# ADC_8CH.net
KiCad netlist of a schematic drawn in Altium Designer
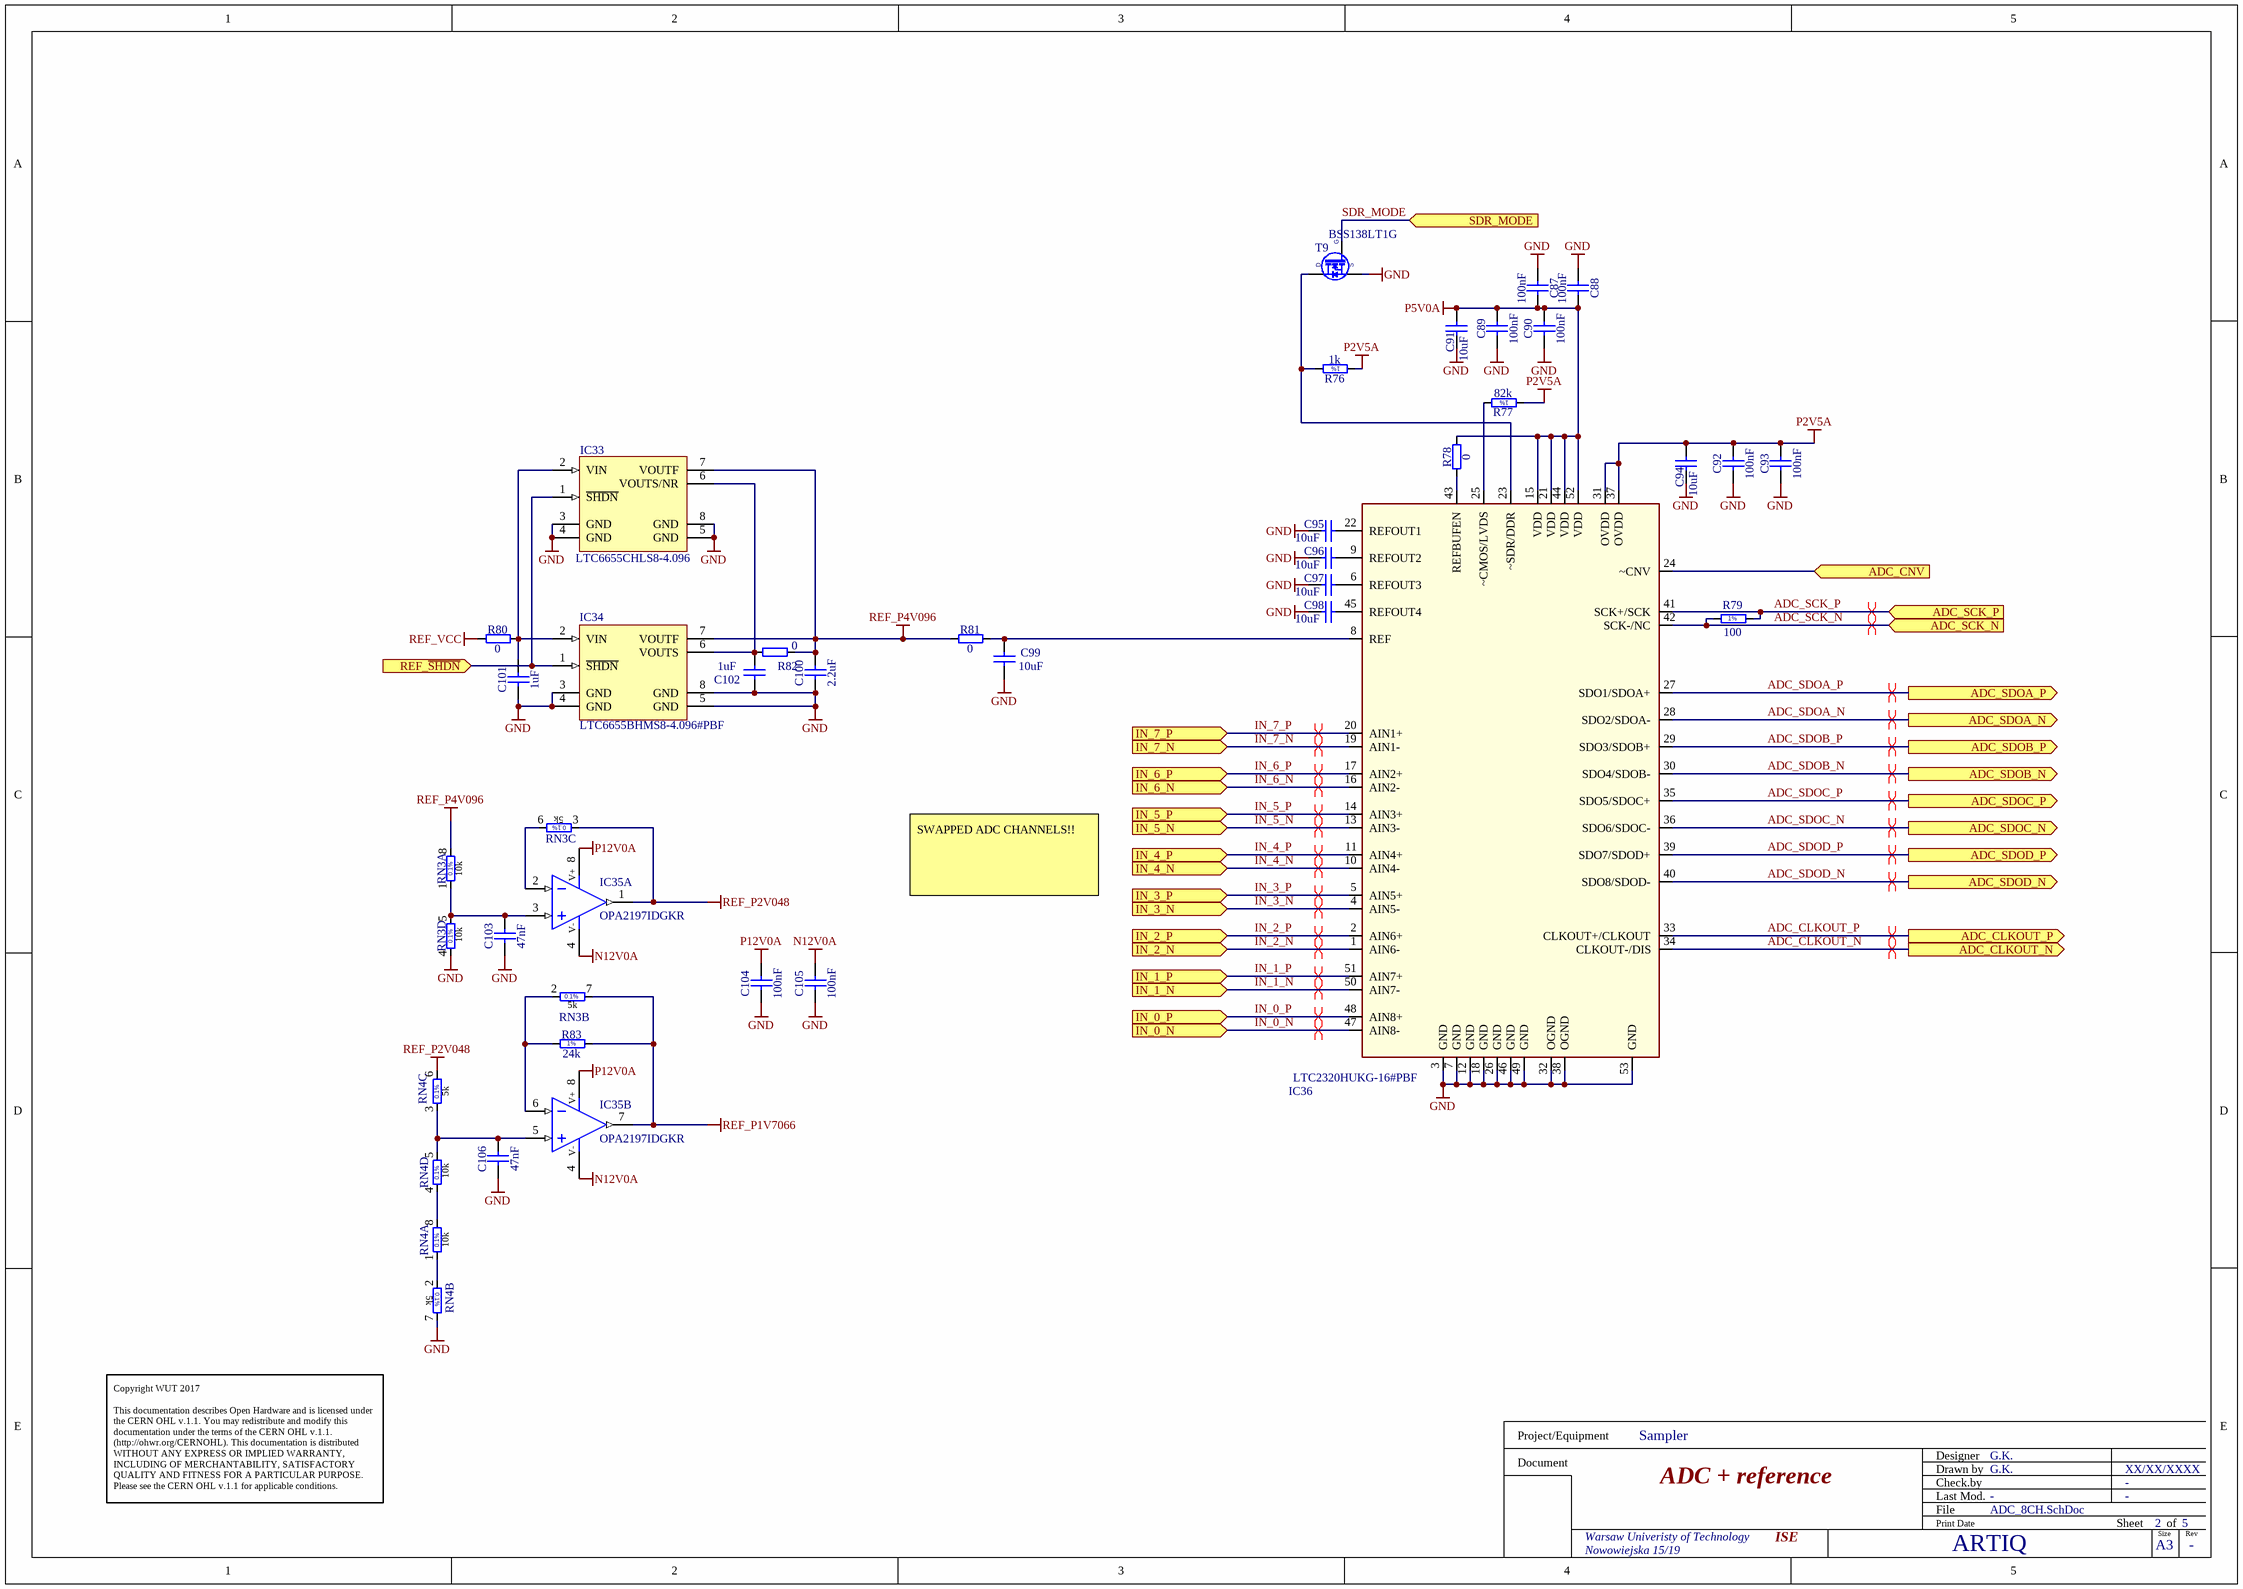
[diagram p0: ADC_8CH.SchDoc]

(export (version "E")
  (design (tool "Eeschema 10.0.6"))
  (components
    (comp (ref "C87")
      (value "100nF")
      (footprint "CAPC1608X87N")
      (description "Non-polarised capacitor")
      (fields
        (field (name "PART NUMBER") "CC0603_100NF_50V_10%_X7R")
        (field (name "VOLTAGE") "50V")
        (field (name "AUTHOR") "CERN DEM JLC")
      )
      (libsource (lib "Capacitors") (part "Capacitor - non polarized"))
    )
    (comp (ref "C88")
      (value "100nF")
      (footprint "CAPC1608X87N")
      (description "Non-polarised capacitor")
      (fields
        (field (name "PART NUMBER") "CC0603_100NF_50V_10%_X7R")
        (field (name "VOLTAGE") "50V")
        (field (name "AUTHOR") "CERN DEM JLC")
      )
      (libsource (lib "Capacitors") (part "Capacitor - non polarized"))
    )
    (comp (ref "C89")
      (value "100nF")
      (footprint "CAPC1608X87N")
      (description "Non-polarised capacitor")
      (fields
        (field (name "PART NUMBER") "CC0603_100NF_50V_10%_X7R")
        (field (name "VOLTAGE") "50V")
        (field (name "AUTHOR") "CERN DEM JLC")
      )
      (libsource (lib "Capacitors") (part "Capacitor - non polarized"))
    )
    (comp (ref "C90")
      (value "100nF")
      (footprint "CAPC1608X87N")
      (description "Non-polarised capacitor")
      (fields
        (field (name "PART NUMBER") "CC0603_100NF_50V_10%_X7R")
        (field (name "VOLTAGE") "50V")
        (field (name "AUTHOR") "CERN DEM JLC")
      )
      (libsource (lib "Capacitors") (part "Capacitor - non polarized"))
    )
    (comp (ref "C91")
      (value "10uF")
      (footprint "CAPC2012X95N")
      (description "Non-polarised capacitor")
      (fields
        (field (name "PART NUMBER") "CC0805_10UF_25V_10%_X5R")
        (field (name "VOLTAGE") "25V")
        (field (name "AUTHOR") "CERN DEM JLC")
      )
      (libsource (lib "Capacitors") (part "Capacitor - non polarized"))
    )
    (comp (ref "C92")
      (value "100nF")
      (footprint "CAPC1608X87N")
      (description "Non-polarised capacitor")
      (fields
        (field (name "PART NUMBER") "CC0603_100NF_50V_10%_X7R")
        (field (name "VOLTAGE") "50V")
        (field (name "AUTHOR") "CERN DEM JLC")
      )
      (libsource (lib "Capacitors") (part "Capacitor - non polarized"))
    )
    (comp (ref "C93")
      (value "100nF")
      (footprint "CAPC1608X87N")
      (description "Non-polarised capacitor")
      (fields
        (field (name "PART NUMBER") "CC0603_100NF_50V_10%_X7R")
        (field (name "VOLTAGE") "50V")
        (field (name "AUTHOR") "CERN DEM JLC")
      )
      (libsource (lib "Capacitors") (part "Capacitor - non polarized"))
    )
    (comp (ref "C94")
      (value "10uF")
      (footprint "CAPC2012X95N")
      (description "Non-polarised capacitor")
      (fields
        (field (name "PART NUMBER") "CC0805_10UF_25V_10%_X5R")
        (field (name "VOLTAGE") "25V")
        (field (name "AUTHOR") "CERN DEM JLC")
      )
      (libsource (lib "Capacitors") (part "Capacitor - non polarized"))
    )
    (comp (ref "C95")
      (value "10uF")
      (footprint "CAPC2012X95N")
      (description "Non-polarised capacitor")
      (fields
        (field (name "PART NUMBER") "CC0805_10UF_25V_10%_X5R")
        (field (name "VOLTAGE") "25V")
        (field (name "AUTHOR") "CERN DEM JLC")
      )
      (libsource (lib "Capacitors") (part "Capacitor - non polarized"))
    )
    (comp (ref "C96")
      (value "10uF")
      (footprint "CAPC2012X95N")
      (description "Non-polarised capacitor")
      (fields
        (field (name "PART NUMBER") "CC0805_10UF_25V_10%_X5R")
        (field (name "VOLTAGE") "25V")
        (field (name "AUTHOR") "CERN DEM JLC")
      )
      (libsource (lib "Capacitors") (part "Capacitor - non polarized"))
    )
    (comp (ref "C97")
      (value "10uF")
      (footprint "CAPC2012X95N")
      (description "Non-polarised capacitor")
      (fields
        (field (name "PART NUMBER") "CC0805_10UF_25V_10%_X5R")
        (field (name "VOLTAGE") "25V")
        (field (name "AUTHOR") "CERN DEM JLC")
      )
      (libsource (lib "Capacitors") (part "Capacitor - non polarized"))
    )
    (comp (ref "C98")
      (value "10uF")
      (footprint "CAPC2012X95N")
      (description "Non-polarised capacitor")
      (fields
        (field (name "PART NUMBER") "CC0805_10UF_25V_10%_X5R")
        (field (name "VOLTAGE") "25V")
        (field (name "AUTHOR") "CERN DEM JLC")
      )
      (libsource (lib "Capacitors") (part "Capacitor - non polarized"))
    )
    (comp (ref "C99")
      (value "10uF")
      (footprint "CAPC2012X95N")
      (description "Non-polarised capacitor")
      (fields
        (field (name "PART NUMBER") "CC0805_10UF_25V_10%_X5R")
        (field (name "VOLTAGE") "25V")
        (field (name "AUTHOR") "CERN DEM JLC")
      )
      (libsource (lib "Capacitors") (part "Capacitor - non polarized"))
    )
    (comp (ref "C100")
      (value "2.2uF")
      (footprint "CAPC1608X87N")
      (description "Non-polarised capacitor")
      (fields
        (field (name "PART NUMBER") "CC0603_2.2UF_16V_10%_X5R")
        (field (name "VOLTAGE") "16V")
        (field (name "AUTHOR") "CERN DEM JLC")
      )
      (libsource (lib "Capacitors") (part "Capacitor - non polarized"))
    )
    (comp (ref "C101")
      (value "1uF")
      (footprint "CAPC1608X87N")
      (description "Non-polarised capacitor")
      (fields
        (field (name "PART NUMBER") "CC0603_1UF_25V_10%_X7R")
        (field (name "VOLTAGE") "25V")
        (field (name "AUTHOR") "CERN DEM JLC")
      )
      (libsource (lib "Capacitors") (part "Capacitor - non polarized"))
    )
    (comp (ref "C102")
      (value "1uF")
      (footprint "CAPC1608X87N")
      (description "Non-polarised capacitor")
      (fields
        (field (name "PART NUMBER") "CC0603_1UF_25V_10%_X7R")
        (field (name "VOLTAGE") "25V")
        (field (name "AUTHOR") "CERN DEM JLC")
      )
      (libsource (lib "Capacitors") (part "Capacitor - non polarized"))
    )
    (comp (ref "C103")
      (value "47nF")
      (footprint "CAPC2012X135N")
      (description "Non-polarised capacitor")
      (fields
        (field (name "PART NUMBER") "CC0805_47NF_25V_5%_C0G")
        (field (name "VOLTAGE") "25V")
        (field (name "AUTHOR") "CERN DEM JLC")
      )
      (libsource (lib "Capacitors") (part "Capacitor - non polarized"))
    )
    (comp (ref "C104")
      (value "100nF")
      (footprint "CAPC1005X55N")
      (description "Non-polarised capacitor")
      (fields
        (field (name "PART NUMBER") "CC0402_100NF_16V_10%_X5R")
        (field (name "VOLTAGE") "16V")
        (field (name "AUTHOR") "CERN DEM JLC")
      )
      (libsource (lib "Capacitors") (part "Capacitor - non polarized"))
    )
    (comp (ref "C105")
      (value "100nF")
      (footprint "CAPC1005X55N")
      (description "Non-polarised capacitor")
      (fields
        (field (name "PART NUMBER") "CC0402_100NF_16V_10%_X5R")
        (field (name "VOLTAGE") "16V")
        (field (name "AUTHOR") "CERN DEM JLC")
      )
      (libsource (lib "Capacitors") (part "Capacitor - non polarized"))
    )
    (comp (ref "C106")
      (value "47nF")
      (footprint "CAPC2012X135N")
      (description "Non-polarised capacitor")
      (fields
        (field (name "PART NUMBER") "CC0805_47NF_25V_5%_C0G")
        (field (name "VOLTAGE") "25V")
        (field (name "AUTHOR") "CERN DEM JLC")
      )
      (libsource (lib "Capacitors") (part "Capacitor - non polarized"))
    )
    (comp (ref "IC33")
      (value "LTC6655CHLS8-4.096")
      (footprint "LCCS127P500X500X145-8N")
      (description "4.096, 1uA Precision Voltage Reference")
      (fields
        (field (name "PART NUMBER") "LTC6655CHLS8-4.096#PBF")
        (field (name "MANUFACTURER") "LINEAR TECHNOLOGY")
        (field (name "AUTHOR") "GK")
      )
      (libsource (lib "ICs_Analog_Interfaces") (part "REF_LTC6655CHLS8-4.096"))
    )
    (comp (ref "IC34")
      (value "LTC6655BHMS8-4.096#PBF")
      (footprint "SOP65P490X110-8N")
      (description "0.25ppm Noise, Low Drift Precision Buffered Voltage Reference")
      (fields (field (name "MANUFACTURER") "LINEAR TECHNOLOGY") (field (name "AUTHOR") "GK"))
      (libsource (lib "LIBRARY_SCH") (part "REF_LTC6655"))
    )
    (comp (ref "IC35")
      (value "OPA2197IDGKR")
      (footprint "SOP65P490X110-8N")
      (description "36-V, Precision, Rail-to-Rail Input Output, Low Offset Voltage Op Amp 8-VSSOP")
      (fields (field (name "MANUFACTURER") "TEXAS INSTRUMENTS") (field (name "AUTHOR") "GK"))
      (libsource (lib "LIBRARY_SCH") (part "OA_OPA2197IDGKR"))
    )
    (comp (ref "IC36")
      (value "LTC2320HUKG-16#PBF")
      (footprint "QFN50P700X800X80_HS-53M")
      (description "Octal, 16-Bit, 1.5Msps/Ch  Simultaneous Sampling ADC")
      (fields (field (name "MANUFACTURER") "LINEAR TECHNOLOGY") (field (name "AUTHOR") "GK"))
      (libsource (lib "LIBRARY_SCH") (part "ADC_LTC2320HUKG-16"))
    )
    (comp (ref "R76")
      (value "1k")
      (footprint "RESC1608X55N")
      (description "Resistor - 1%")
      (fields
        (field (name "PART NUMBER") "R0603_1K_1%_0.1W_100PPM")
        (field (name "POWER") "0.1W")
        (field (name "AUTHOR") "CERN DEM JLC")
      )
      (libsource (lib "Resistors") (part "Resistor - 1%"))
    )
    (comp (ref "R77")
      (value "82k")
      (footprint "RESC1608X55N")
      (description "Resistor - 1%")
      (fields
        (field (name "PART NUMBER") "R0603_82K_1%_0.1W_100PPM")
        (field (name "POWER") "0.1W")
        (field (name "AUTHOR") "CERN DEM JLC")
      )
      (libsource (lib "Resistors") (part "Resistor - 1%"))
    )
    (comp (ref "R78")
      (value "0")
      (footprint "RESC1005X40N")
      (description "Resistor")
      (fields
        (field (name "PART NUMBER") "R0402_0R_JUMPER")
        (field (name "MANUFACTURER") "GENERIC")
        (field (name "AUTHOR") "CERN DEM JLC")
      )
      (libsource (lib "Resistors") (part "Resistor"))
    )
    (comp (ref "R79")
      (value "100")
      (footprint "RESC1005X40N")
      (description "Resistor - 1%")
      (fields
        (field (name "PART NUMBER") "R0402_100R_1%_0.1W_100PPM")
        (field (name "POWER") "0.1W")
        (field (name "AUTHOR") "CERN DEM JLC")
      )
      (libsource (lib "Resistors") (part "Resistor - 1%"))
    )
    (comp (ref "R80")
      (value "0")
      (footprint "RESC1005X40N")
      (description "Resistor")
      (fields
        (field (name "PART NUMBER") "R0402_0R_JUMPER")
        (field (name "MANUFACTURER") "GENERIC")
        (field (name "AUTHOR") "CERN DEM JLC")
      )
      (libsource (lib "Resistors") (part "Resistor"))
    )
    (comp (ref "R81")
      (value "0")
      (footprint "RESC1005X40N")
      (description "Resistor")
      (fields
        (field (name "PART NUMBER") "R0402_0R_JUMPER")
        (field (name "MANUFACTURER") "GENERIC")
        (field (name "AUTHOR") "CERN DEM JLC")
      )
      (libsource (lib "Resistors") (part "Resistor"))
    )
    (comp (ref "R82")
      (value "0")
      (footprint "RESC1005X40N")
      (description "Resistor")
      (fields
        (field (name "PART NUMBER") "R0402_0R_JUMPER")
        (field (name "MANUFACTURER") "GENERIC")
        (field (name "AUTHOR") "CERN DEM JLC")
      )
      (libsource (lib "Resistors") (part "Resistor"))
    )
    (comp (ref "R83")
      (value "24k")
      (footprint "RESC1608X55N")
      (description "Resistor - 1%")
      (fields
        (field (name "PART NUMBER") "R0603_24K_1%_0.1W_100PPM")
        (field (name "POWER") "0.1W")
        (field (name "AUTHOR") "CERN DEM JLC")
      )
      (libsource (lib "Resistors") (part "Resistor - 1%"))
    )
    (comp (ref "RN3")
      (value "10k 5K 5K 10K")
      (footprint "SOIC127P600X175-8N")
      (description "DIL8 Resistor Network 4 Resistors 10k-5k-5k-10k 0.1%")
      (fields
        (field (name "PART NUMBER") "RN_10K_5K_VISHAY_AORN2-1AT3")
        (field (name "POWER") "4x0.1W")
        (field (name "AUTHOR") "CERN DEM JLC")
      )
      (libsource (lib "Resistors") (part "RN DIL8_4xR_10k-5k-5k-10k_0.1%"))
    )
    (comp (ref "RN4")
      (value "10k 5K 5K 10K")
      (footprint "SOIC127P600X175-8N")
      (description "DIL8 Resistor Network 4 Resistors 10k-5k-5k-10k 0.1%")
      (fields
        (field (name "PART NUMBER") "RN_10K_5K_VISHAY_AORN2-1AT3")
        (field (name "POWER") "4x0.1W")
        (field (name "AUTHOR") "CERN DEM JLC")
      )
      (libsource (lib "Resistors") (part "RN DIL8_4xR_10k-5k-5k-10k_0.1%"))
    )
    (comp (ref "T9")
      (value "BSS138LT1G")
      (footprint "SOT95P240X110-3N")
      (description "N-CHANNEL MOSFET WITH DIODE")
      (fields (field (name "MANUFACTURER") "ON SEMICONDUCTOR") (field (name "AUTHOR") "CERN DEM JLC"))
      (libsource (lib "ICs And Semiconductors") (part "N-MOSFET-D 1G 2S 3D"))
    )
  )
  (nets
    (net (code "1") (name "/ADC_CLKOUT_N") (class "Default")
      (node (ref "IC36") (pin "34") (pinfunction "CLKOUT-/DIS_34") (pintype "passive"))
    )
    (net (code "2") (name "/ADC_CLKOUT_P") (class "Default")
      (node (ref "IC36") (pin "33") (pinfunction "CLKOUT+/CLKOUT_33") (pintype "passive"))
    )
    (net (code "3") (name "/ADC_CNV") (class "Default")
      (node (ref "IC36") (pin "24") (pinfunction "~CNV_24") (pintype "passive"))
    )
    (net (code "4") (name "/ADC_SCK_N") (class "Default")
      (node (ref "IC36") (pin "42") (pinfunction "SCK-/NC_42") (pintype "passive"))
      (node (ref "R79") (pin "1") (pinfunction "1_1") (pintype "passive"))
    )
    (net (code "5") (name "/ADC_SCK_P") (class "Default")
      (node (ref "IC36") (pin "41") (pinfunction "SCK+/SCK_41") (pintype "passive"))
      (node (ref "R79") (pin "2") (pinfunction "2_2") (pintype "passive"))
    )
    (net (code "6") (name "/ADC_SDOA_N") (class "Default")
      (node (ref "IC36") (pin "28") (pinfunction "SDO2/SDOA-_28") (pintype "passive"))
    )
    (net (code "7") (name "/ADC_SDOA_P") (class "Default")
      (node (ref "IC36") (pin "27") (pinfunction "SDO1/SDOA+_27") (pintype "passive"))
    )
    (net (code "8") (name "/ADC_SDOB_N") (class "Default")
      (node (ref "IC36") (pin "30") (pinfunction "SDO4/SDOB-_30") (pintype "passive"))
    )
    (net (code "9") (name "/ADC_SDOB_P") (class "Default")
      (node (ref "IC36") (pin "29") (pinfunction "SDO3/SDOB+_29") (pintype "passive"))
    )
    (net (code "10") (name "/ADC_SDOC_N") (class "Default")
      (node (ref "IC36") (pin "36") (pinfunction "SDO6/SDOC-_36") (pintype "passive"))
    )
    (net (code "11") (name "/ADC_SDOC_P") (class "Default")
      (node (ref "IC36") (pin "35") (pinfunction "SDO5/SDOC+_35") (pintype "passive"))
    )
    (net (code "12") (name "/ADC_SDOD_N") (class "Default")
      (node (ref "IC36") (pin "40") (pinfunction "SDO8/SDOD-_40") (pintype "passive"))
    )
    (net (code "13") (name "/ADC_SDOD_P") (class "Default")
      (node (ref "IC36") (pin "39") (pinfunction "SDO7/SDOD+_39") (pintype "passive"))
    )
    (net (code "14") (name "/IN_0_N") (class "Default")
      (node (ref "IC36") (pin "47") (pinfunction "AIN8-_47") (pintype "passive"))
    )
    (net (code "15") (name "/IN_0_P") (class "Default")
      (node (ref "IC36") (pin "48") (pinfunction "AIN8+_48") (pintype "passive"))
    )
    (net (code "16") (name "/IN_1_N") (class "Default")
      (node (ref "IC36") (pin "50") (pinfunction "AIN7-_50") (pintype "passive"))
    )
    (net (code "17") (name "/IN_1_P") (class "Default")
      (node (ref "IC36") (pin "51") (pinfunction "AIN7+_51") (pintype "passive"))
    )
    (net (code "18") (name "/IN_2_N") (class "Default")
      (node (ref "IC36") (pin "1") (pinfunction "AIN6-_1") (pintype "passive"))
    )
    (net (code "19") (name "/IN_2_P") (class "Default")
      (node (ref "IC36") (pin "2") (pinfunction "AIN6+_2") (pintype "passive"))
    )
    (net (code "20") (name "/IN_3_N") (class "Default")
      (node (ref "IC36") (pin "4") (pinfunction "AIN5-_4") (pintype "passive"))
    )
    (net (code "21") (name "/IN_3_P") (class "Default")
      (node (ref "IC36") (pin "5") (pinfunction "AIN5+_5") (pintype "passive"))
    )
    (net (code "22") (name "/IN_4_N") (class "Default")
      (node (ref "IC36") (pin "10") (pinfunction "AIN4-_10") (pintype "passive"))
    )
    (net (code "23") (name "/IN_4_P") (class "Default")
      (node (ref "IC36") (pin "11") (pinfunction "AIN4+_11") (pintype "passive"))
    )
    (net (code "24") (name "/IN_5_N") (class "Default")
      (node (ref "IC36") (pin "13") (pinfunction "AIN3-_13") (pintype "passive"))
    )
    (net (code "25") (name "/IN_5_P") (class "Default")
      (node (ref "IC36") (pin "14") (pinfunction "AIN3+_14") (pintype "passive"))
    )
    (net (code "26") (name "/IN_6_N") (class "Default")
      (node (ref "IC36") (pin "16") (pinfunction "AIN2-_16") (pintype "passive"))
    )
    (net (code "27") (name "/IN_6_P") (class "Default")
      (node (ref "IC36") (pin "17") (pinfunction "AIN2+_17") (pintype "passive"))
    )
    (net (code "28") (name "/IN_7_N") (class "Default")
      (node (ref "IC36") (pin "19") (pinfunction "AIN1-_19") (pintype "passive"))
    )
    (net (code "29") (name "/IN_7_P") (class "Default")
      (node (ref "IC36") (pin "20") (pinfunction "AIN1+_20") (pintype "passive"))
    )
    (net (code "30") (name "/REF_~{SHDN}") (class "Default")
      (node (ref "IC33") (pin "1") (pinfunction "~{SHDN}_1") (pintype "input"))
      (node (ref "IC34") (pin "1") (pinfunction "~{SHDN}_1") (pintype "input"))
    )
    (net (code "31") (name "/SDR_MODE") (class "Default")
      (node (ref "T9") (pin "1") (pinfunction "G_1") (pintype "passive"))
    )
    (net (code "32") (name "GND") (class "Default")
      (node (ref "C100") (pin "1") (pinfunction "1_1") (pintype "passive"))
      (node (ref "C101") (pin "1") (pinfunction "1_1") (pintype "passive"))
      (node (ref "C102") (pin "1") (pinfunction "1_1") (pintype "passive"))
      (node (ref "C103") (pin "1") (pinfunction "1_1") (pintype "passive"))
      (node (ref "C104") (pin "1") (pinfunction "1_1") (pintype "passive"))
      (node (ref "C105") (pin "1") (pinfunction "1_1") (pintype "passive"))
      (node (ref "C106") (pin "1") (pinfunction "1_1") (pintype "passive"))
      (node (ref "C87") (pin "1") (pinfunction "1_1") (pintype "passive"))
      (node (ref "C88") (pin "1") (pinfunction "1_1") (pintype "passive"))
      (node (ref "C89") (pin "1") (pinfunction "1_1") (pintype "passive"))
      (node (ref "C90") (pin "1") (pinfunction "1_1") (pintype "passive"))
      (node (ref "C91") (pin "1") (pinfunction "1_1") (pintype "passive"))
      (node (ref "C92") (pin "1") (pinfunction "1_1") (pintype "passive"))
      (node (ref "C93") (pin "1") (pinfunction "1_1") (pintype "passive"))
      (node (ref "C94") (pin "1") (pinfunction "1_1") (pintype "passive"))
      (node (ref "C95") (pin "1") (pinfunction "1_1") (pintype "passive"))
      (node (ref "C96") (pin "1") (pinfunction "1_1") (pintype "passive"))
      (node (ref "C97") (pin "1") (pinfunction "1_1") (pintype "passive"))
      (node (ref "C98") (pin "1") (pinfunction "1_1") (pintype "passive"))
      (node (ref "C99") (pin "1") (pinfunction "1_1") (pintype "passive"))
      (node (ref "IC33") (pin "3") (pinfunction "GND_3") (pintype "power_in"))
      (node (ref "IC33") (pin "4") (pinfunction "GND_4") (pintype "power_in"))
      (node (ref "IC33") (pin "5") (pinfunction "GND_5") (pintype "power_in"))
      (node (ref "IC33") (pin "8") (pinfunction "GND_8") (pintype "power_in"))
      (node (ref "IC34") (pin "3") (pinfunction "GND_3") (pintype "power_in"))
      (node (ref "IC34") (pin "4") (pinfunction "GND_4") (pintype "power_in"))
      (node (ref "IC34") (pin "5") (pinfunction "GND_5") (pintype "power_in"))
      (node (ref "IC34") (pin "8") (pinfunction "GND_8") (pintype "power_in"))
      (node (ref "IC36") (pin "12") (pinfunction "GND_12") (pintype "passive"))
      (node (ref "IC36") (pin "18") (pinfunction "GND_18") (pintype "passive"))
      (node (ref "IC36") (pin "26") (pinfunction "GND_26") (pintype "passive"))
      (node (ref "IC36") (pin "3") (pinfunction "GND_3") (pintype "passive"))
      (node (ref "IC36") (pin "32") (pinfunction "OGND_32") (pintype "passive"))
      (node (ref "IC36") (pin "38") (pinfunction "OGND_38") (pintype "passive"))
      (node (ref "IC36") (pin "46") (pinfunction "GND_46") (pintype "passive"))
      (node (ref "IC36") (pin "49") (pinfunction "GND_49") (pintype "passive"))
      (node (ref "IC36") (pin "53") (pinfunction "GND_53") (pintype "passive"))
      (node (ref "IC36") (pin "7") (pinfunction "GND_7") (pintype "passive"))
      (node (ref "RN3") (pin "4") (pinfunction "4_4") (pintype "passive"))
      (node (ref "RN4") (pin "7") (pinfunction "7_7") (pintype "passive"))
      (node (ref "T9") (pin "2") (pinfunction "S_2") (pintype "passive"))
    )
    (net (code "33") (name "N12V0A") (class "Default")
      (node (ref "C105") (pin "2") (pinfunction "2_2") (pintype "passive"))
      (node (ref "IC35") (pin "4") (pinfunction "V-_4") (pintype "power_in"))
    )
    (net (code "34") (name "Net-(IC33-VIN)") (class "Default")
      (node (ref "C101") (pin "2") (pinfunction "2_2") (pintype "passive"))
      (node (ref "IC33") (pin "2") (pinfunction "VIN_2") (pintype "input"))
      (node (ref "IC34") (pin "2") (pinfunction "VIN_2") (pintype "input"))
      (node (ref "R80") (pin "2") (pinfunction "2_2") (pintype "passive"))
    )
    (net (code "35") (name "Net-(IC33-VOUTS{slash}NR)") (class "Default")
      (node (ref "C102") (pin "2") (pinfunction "2_2") (pintype "passive"))
      (node (ref "IC33") (pin "6") (pinfunction "VOUTS/NR_6") (pintype "power_in"))
      (node (ref "IC34") (pin "6") (pinfunction "VOUTS_6") (pintype "power_in"))
      (node (ref "R82") (pin "1") (pinfunction "1_1") (pintype "passive"))
    )
    (net (code "36") (name "Net-(IC35A-IN+)") (class "Default")
      (node (ref "C103") (pin "2") (pinfunction "2_2") (pintype "passive"))
      (node (ref "IC35") (pin "3") (pinfunction "IN+_3") (pintype "input"))
      (node (ref "RN3") (pin "1") (pinfunction "1_1") (pintype "passive"))
      (node (ref "RN3") (pin "5") (pinfunction "5_5") (pintype "passive"))
    )
    (net (code "37") (name "Net-(IC35A-IN-)") (class "Default")
      (node (ref "IC35") (pin "2") (pinfunction "IN-_2") (pintype "input"))
      (node (ref "RN3") (pin "6") (pinfunction "6_6") (pintype "passive"))
    )
    (net (code "38") (name "Net-(IC35B-IN+)") (class "Default")
      (node (ref "C106") (pin "2") (pinfunction "2_2") (pintype "passive"))
      (node (ref "IC35") (pin "5") (pinfunction "IN+_5") (pintype "input"))
      (node (ref "RN4") (pin "3") (pinfunction "3_3") (pintype "passive"))
      (node (ref "RN4") (pin "5") (pinfunction "5_5") (pintype "passive"))
    )
    (net (code "39") (name "Net-(IC35B-IN-)") (class "Default")
      (node (ref "IC35") (pin "6") (pinfunction "IN-_6") (pintype "input"))
      (node (ref "R83") (pin "1") (pinfunction "1_1") (pintype "passive"))
      (node (ref "RN3") (pin "2") (pinfunction "2_2") (pintype "passive"))
    )
    (net (code "40") (name "Net-(IC36-REF)") (class "Default")
      (node (ref "C99") (pin "2") (pinfunction "2_2") (pintype "passive"))
      (node (ref "IC36") (pin "8") (pinfunction "REF_8") (pintype "passive"))
      (node (ref "R81") (pin "2") (pinfunction "2_2") (pintype "passive"))
    )
    (net (code "41") (name "Net-(IC36-REFBUFEN)") (class "Default")
      (node (ref "IC36") (pin "43") (pinfunction "REFBUFEN_43") (pintype "passive"))
      (node (ref "R78") (pin "1") (pinfunction "1_1") (pintype "passive"))
    )
    (net (code "42") (name "Net-(IC36-REFOUT1)") (class "Default")
      (node (ref "C95") (pin "2") (pinfunction "2_2") (pintype "passive"))
      (node (ref "IC36") (pin "22") (pinfunction "REFOUT1_22") (pintype "passive"))
    )
    (net (code "43") (name "Net-(IC36-REFOUT2)") (class "Default")
      (node (ref "C96") (pin "2") (pinfunction "2_2") (pintype "passive"))
      (node (ref "IC36") (pin "9") (pinfunction "REFOUT2_9") (pintype "passive"))
    )
    (net (code "44") (name "Net-(IC36-REFOUT3)") (class "Default")
      (node (ref "C97") (pin "2") (pinfunction "2_2") (pintype "passive"))
      (node (ref "IC36") (pin "6") (pinfunction "REFOUT3_6") (pintype "passive"))
    )
    (net (code "45") (name "Net-(IC36-REFOUT4)") (class "Default")
      (node (ref "C98") (pin "2") (pinfunction "2_2") (pintype "passive"))
      (node (ref "IC36") (pin "45") (pinfunction "REFOUT4_45") (pintype "passive"))
    )
    (net (code "46") (name "Net-(IC36-~CMOS{slash}LVDS)") (class "Default")
      (node (ref "IC36") (pin "25") (pinfunction "~CMOS/LVDS_25") (pintype "passive"))
      (node (ref "R77") (pin "2") (pinfunction "2_2") (pintype "passive"))
    )
    (net (code "47") (name "Net-(IC36-~SDR{slash}DDR)") (class "Default")
      (node (ref "IC36") (pin "23") (pinfunction "~SDR/DDR_23") (pintype "passive"))
      (node (ref "R76") (pin "2") (pinfunction "2_2") (pintype "passive"))
      (node (ref "T9") (pin "3") (pinfunction "D_3") (pintype "passive"))
    )
    (net (code "48") (name "Net-(RN4-Pad1)") (class "Default")
      (node (ref "RN4") (pin "1") (pinfunction "1_1") (pintype "passive"))
      (node (ref "RN4") (pin "2") (pinfunction "2_2") (pintype "passive"))
    )
    (net (code "49") (name "Net-(RN4-Pad4)") (class "Default")
      (node (ref "RN4") (pin "4") (pinfunction "4_4") (pintype "passive"))
      (node (ref "RN4") (pin "8") (pinfunction "8_8") (pintype "passive"))
    )
    (net (code "50") (name "P2V5A") (class "Default")
      (node (ref "C92") (pin "2") (pinfunction "2_2") (pintype "passive"))
      (node (ref "C93") (pin "2") (pinfunction "2_2") (pintype "passive"))
      (node (ref "C94") (pin "2") (pinfunction "2_2") (pintype "passive"))
      (node (ref "IC36") (pin "31") (pinfunction "OVDD_31") (pintype "passive"))
      (node (ref "IC36") (pin "37") (pinfunction "OVDD_37") (pintype "passive"))
      (node (ref "R76") (pin "1") (pinfunction "1_1") (pintype "passive"))
      (node (ref "R77") (pin "1") (pinfunction "1_1") (pintype "passive"))
    )
    (net (code "51") (name "P5V0A") (class "Default")
      (node (ref "C87") (pin "2") (pinfunction "2_2") (pintype "passive"))
      (node (ref "C88") (pin "2") (pinfunction "2_2") (pintype "passive"))
      (node (ref "C89") (pin "2") (pinfunction "2_2") (pintype "passive"))
      (node (ref "C90") (pin "2") (pinfunction "2_2") (pintype "passive"))
      (node (ref "C91") (pin "2") (pinfunction "2_2") (pintype "passive"))
      (node (ref "IC36") (pin "15") (pinfunction "VDD_15") (pintype "passive"))
      (node (ref "IC36") (pin "21") (pinfunction "VDD_21") (pintype "passive"))
      (node (ref "IC36") (pin "44") (pinfunction "VDD_44") (pintype "passive"))
      (node (ref "IC36") (pin "52") (pinfunction "VDD_52") (pintype "passive"))
      (node (ref "R78") (pin "2") (pinfunction "2_2") (pintype "passive"))
    )
    (net (code "52") (name "P12V0A") (class "Default")
      (node (ref "C104") (pin "2") (pinfunction "2_2") (pintype "passive"))
      (node (ref "IC35") (pin "8") (pinfunction "V+_8") (pintype "power_in"))
    )
    (net (code "53") (name "REF_P1V7066") (class "Default")
      (node (ref "IC35") (pin "7") (pinfunction "OUT_7") (pintype "output"))
      (node (ref "R83") (pin "2") (pinfunction "2_2") (pintype "passive"))
      (node (ref "RN3") (pin "7") (pinfunction "7_7") (pintype "passive"))
    )
    (net (code "54") (name "REF_P2V048") (class "Default")
      (node (ref "IC35") (pin "1") (pinfunction "OUT_1") (pintype "output"))
      (node (ref "RN3") (pin "3") (pinfunction "3_3") (pintype "passive"))
      (node (ref "RN4") (pin "6") (pinfunction "6_6") (pintype "passive"))
    )
    (net (code "55") (name "REF_P4V096") (class "Default")
      (node (ref "C100") (pin "2") (pinfunction "2_2") (pintype "passive"))
      (node (ref "IC33") (pin "7") (pinfunction "VOUTF_7") (pintype "power_in"))
      (node (ref "IC34") (pin "7") (pinfunction "VOUTF_7") (pintype "power_in"))
      (node (ref "R81") (pin "1") (pinfunction "1_1") (pintype "passive"))
      (node (ref "R82") (pin "2") (pinfunction "2_2") (pintype "passive"))
      (node (ref "RN3") (pin "8") (pinfunction "8_8") (pintype "passive"))
    )
    (net (code "56") (name "REF_VCC") (class "Default")
      (node (ref "R80") (pin "1") (pinfunction "1_1") (pintype "passive"))
    )
  )
)
